# shifter.net
KiCad netlist of a schematic drawn in EAGLE
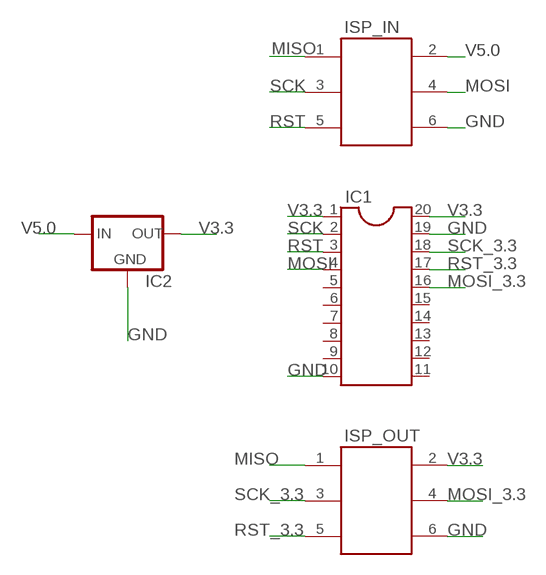
[diagram p0: schematic, sheet 1]

(export (version "E")
  (design (tool "Eeschema 10.0.6"))
  (components
    (comp (ref "IC1")
      (value "DIL20")
      (footprint "eagle-import:DIL20")
      (libsource (lib "eagle-import") (part "DIL20"))
    )
    (comp (ref "IC2")
      (value "MCP1700INLINE")
      (footprint "eagle-import:TO92-INLINE")
      (libsource (lib "eagle-import") (part "MCP1700INLINE"))
    )
    (comp (ref "ISP_IN")
      (value "61200621621")
      (footprint "eagle-import:61200621621")
      (libsource (lib "eagle-import") (part "61200621621"))
    )
    (comp (ref "ISP_OUT")
      (value "61200621621")
      (footprint "eagle-import:61200621621")
      (libsource (lib "eagle-import") (part "61200621621"))
    )
  )
  (nets
    (net (code "1") (name "/GND") (class "Default")
      (node (ref "IC1") (pin "10") (pinfunction "10_10") (pintype "passive"))
      (node (ref "IC1") (pin "19") (pinfunction "19_19") (pintype "passive"))
      (node (ref "IC2") (pin "1") (pinfunction "GND_1") (pintype "input"))
      (node (ref "ISP_IN") (pin "6") (pinfunction "6_6") (pintype "passive"))
      (node (ref "ISP_OUT") (pin "6") (pinfunction "6_6") (pintype "passive"))
    )
    (net (code "2") (name "/MISO") (class "Default")
      (node (ref "ISP_IN") (pin "1") (pinfunction "1_1") (pintype "passive"))
      (node (ref "ISP_OUT") (pin "1") (pinfunction "1_1") (pintype "passive"))
    )
    (net (code "3") (name "/MOSI") (class "Default")
      (node (ref "IC1") (pin "4") (pinfunction "4_4") (pintype "passive"))
      (node (ref "ISP_IN") (pin "4") (pinfunction "4_4") (pintype "passive"))
    )
    (net (code "4") (name "/MOSI_3.3") (class "Default")
      (node (ref "IC1") (pin "16") (pinfunction "16_16") (pintype "passive"))
      (node (ref "ISP_OUT") (pin "4") (pinfunction "4_4") (pintype "passive"))
    )
    (net (code "5") (name "/RST") (class "Default")
      (node (ref "IC1") (pin "3") (pinfunction "3_3") (pintype "passive"))
      (node (ref "ISP_IN") (pin "5") (pinfunction "5_5") (pintype "passive"))
    )
    (net (code "6") (name "/RST_3.3") (class "Default")
      (node (ref "IC1") (pin "17") (pinfunction "17_17") (pintype "passive"))
      (node (ref "ISP_OUT") (pin "5") (pinfunction "5_5") (pintype "passive"))
    )
    (net (code "7") (name "/SCK") (class "Default")
      (node (ref "IC1") (pin "2") (pinfunction "2_2") (pintype "passive"))
      (node (ref "ISP_IN") (pin "3") (pinfunction "3_3") (pintype "passive"))
    )
    (net (code "8") (name "/SCK_3.3") (class "Default")
      (node (ref "IC1") (pin "18") (pinfunction "18_18") (pintype "passive"))
      (node (ref "ISP_OUT") (pin "3") (pinfunction "3_3") (pintype "passive"))
    )
    (net (code "9") (name "/V3.3") (class "Default")
      (node (ref "IC1") (pin "1") (pinfunction "1_1") (pintype "passive"))
      (node (ref "IC1") (pin "20") (pinfunction "20_20") (pintype "passive"))
      (node (ref "IC2") (pin "3") (pinfunction "OUT_3") (pintype "passive"))
      (node (ref "ISP_OUT") (pin "2") (pinfunction "2_2") (pintype "passive"))
    )
    (net (code "10") (name "/V5.0") (class "Default")
      (node (ref "IC2") (pin "2") (pinfunction "IN_2") (pintype "input"))
      (node (ref "ISP_IN") (pin "2") (pinfunction "2_2") (pintype "passive"))
    )
    (net (code "11") (name "unconnected-(IC1-Pad5)") (class "Default")
      (node (ref "IC1") (pin "5") (pinfunction "5_5") (pintype "passive"))
    )
    (net (code "12") (name "unconnected-(IC1-Pad6)") (class "Default")
      (node (ref "IC1") (pin "6") (pinfunction "6_6") (pintype "passive"))
    )
    (net (code "13") (name "unconnected-(IC1-Pad7)") (class "Default")
      (node (ref "IC1") (pin "7") (pinfunction "7_7") (pintype "passive"))
    )
    (net (code "14") (name "unconnected-(IC1-Pad8)") (class "Default")
      (node (ref "IC1") (pin "8") (pinfunction "8_8") (pintype "passive"))
    )
    (net (code "15") (name "unconnected-(IC1-Pad9)") (class "Default")
      (node (ref "IC1") (pin "9") (pinfunction "9_9") (pintype "passive"))
    )
    (net (code "16") (name "unconnected-(IC1-Pad11)") (class "Default")
      (node (ref "IC1") (pin "11") (pinfunction "11_11") (pintype "passive"))
    )
    (net (code "17") (name "unconnected-(IC1-Pad12)") (class "Default")
      (node (ref "IC1") (pin "12") (pinfunction "12_12") (pintype "passive"))
    )
    (net (code "18") (name "unconnected-(IC1-Pad13)") (class "Default")
      (node (ref "IC1") (pin "13") (pinfunction "13_13") (pintype "passive"))
    )
    (net (code "19") (name "unconnected-(IC1-Pad14)") (class "Default")
      (node (ref "IC1") (pin "14") (pinfunction "14_14") (pintype "passive"))
    )
    (net (code "20") (name "unconnected-(IC1-Pad15)") (class "Default")
      (node (ref "IC1") (pin "15") (pinfunction "15_15") (pintype "passive"))
    )
  )
)
